# LooSensorNodeV1.net
KiCad netlist of a schematic drawn in EAGLE
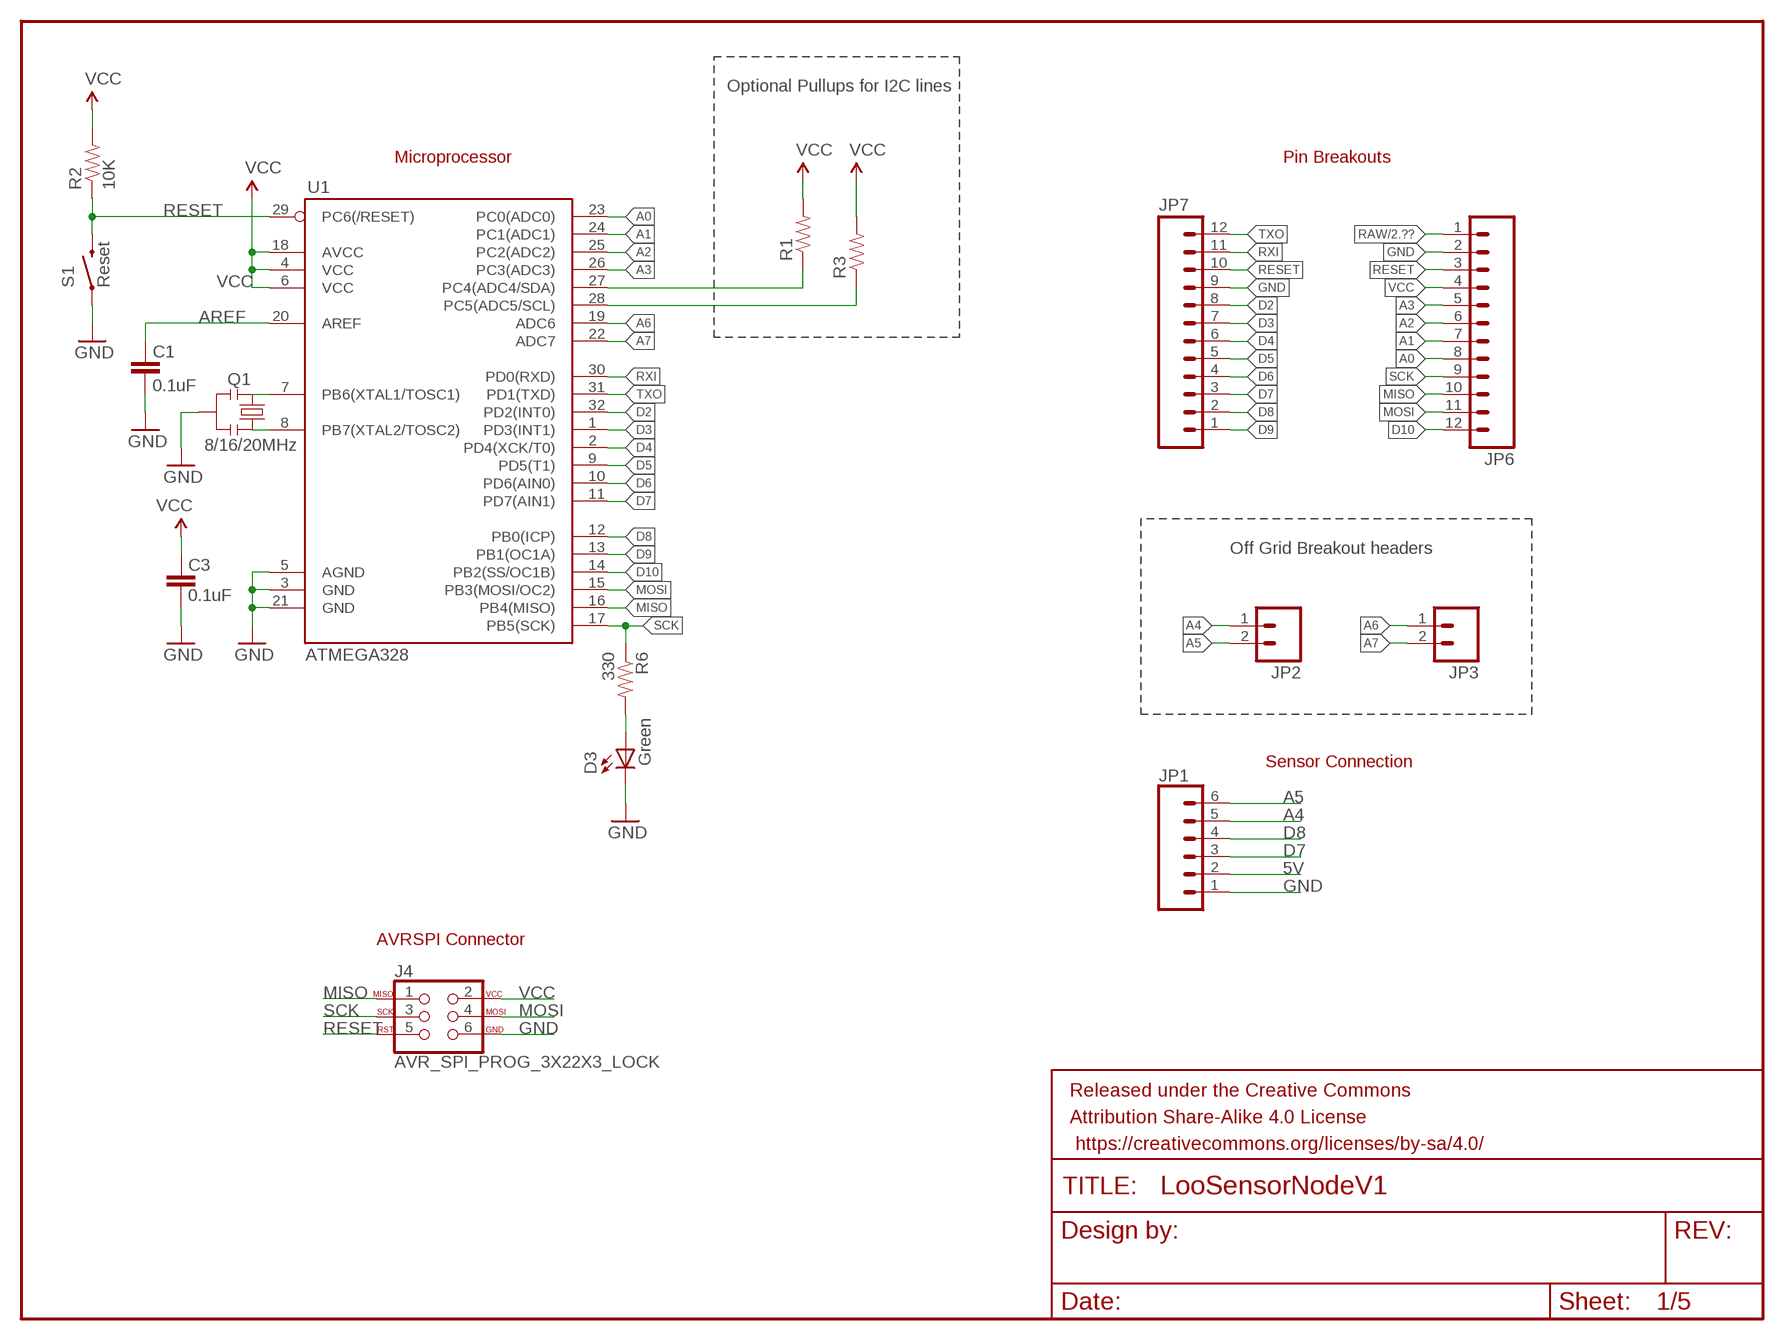
[diagram p0: schematic, sheet 1]
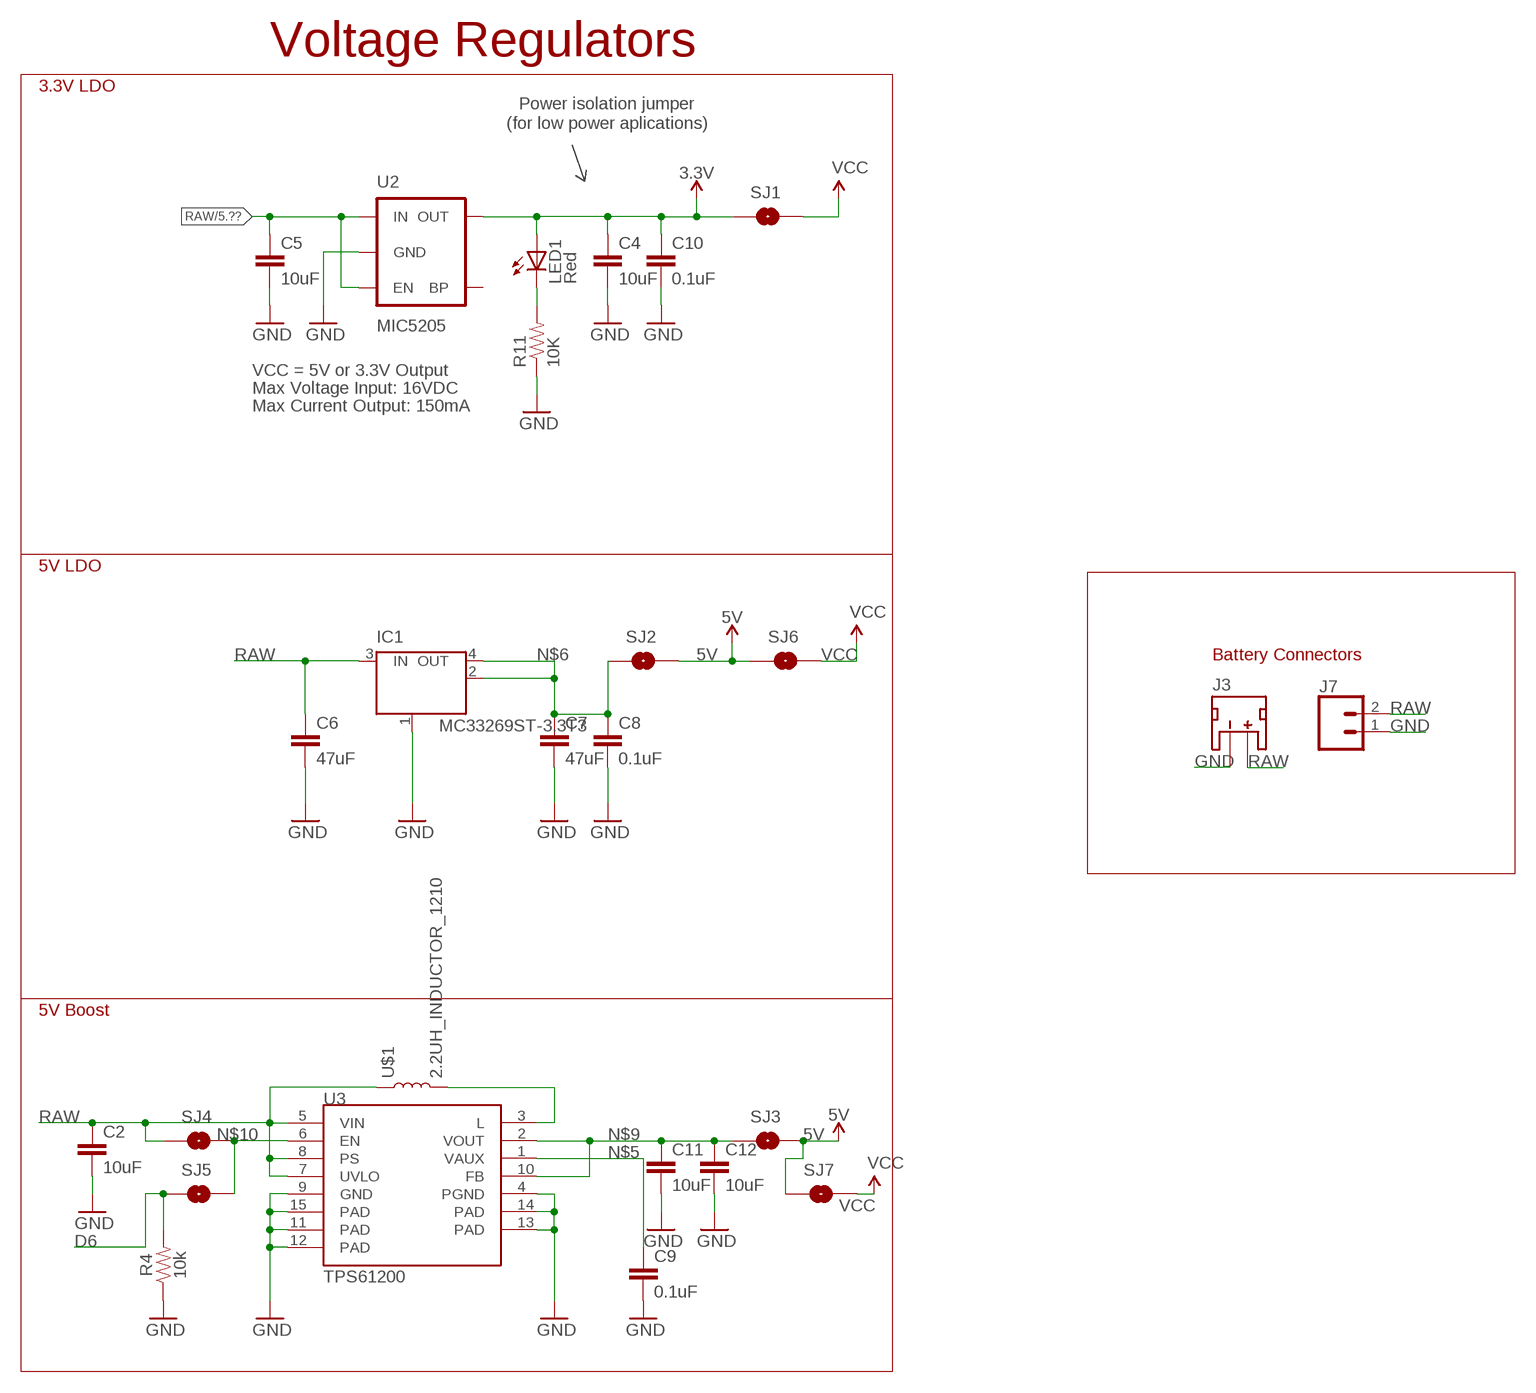
[diagram p1: schematic, sheet 2]
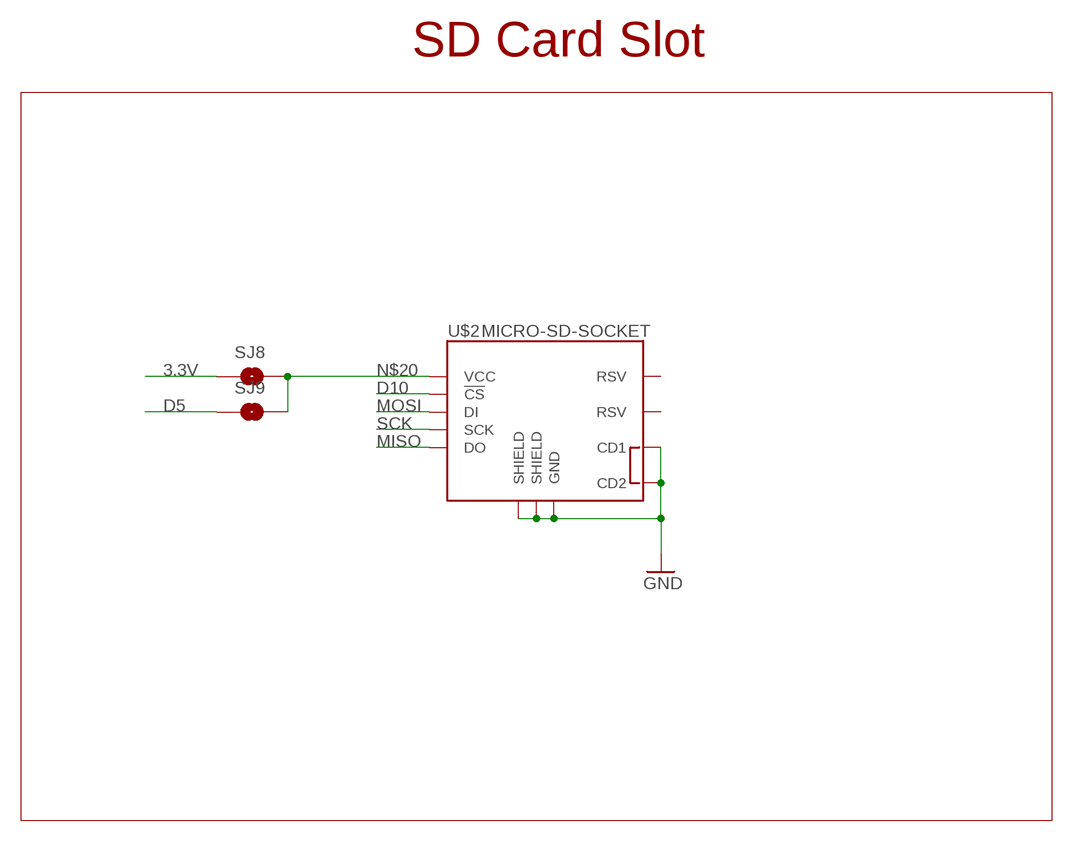
[diagram p2: schematic, sheet 3]
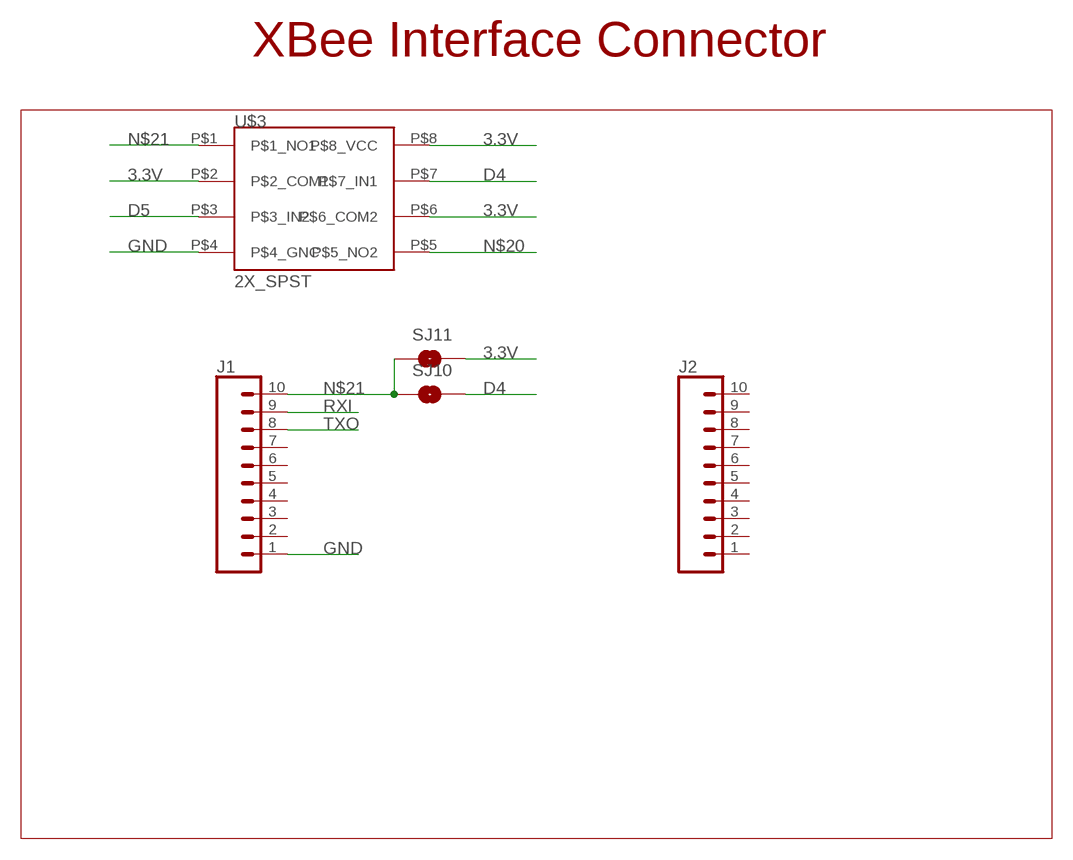
[diagram p3: schematic, sheet 4]
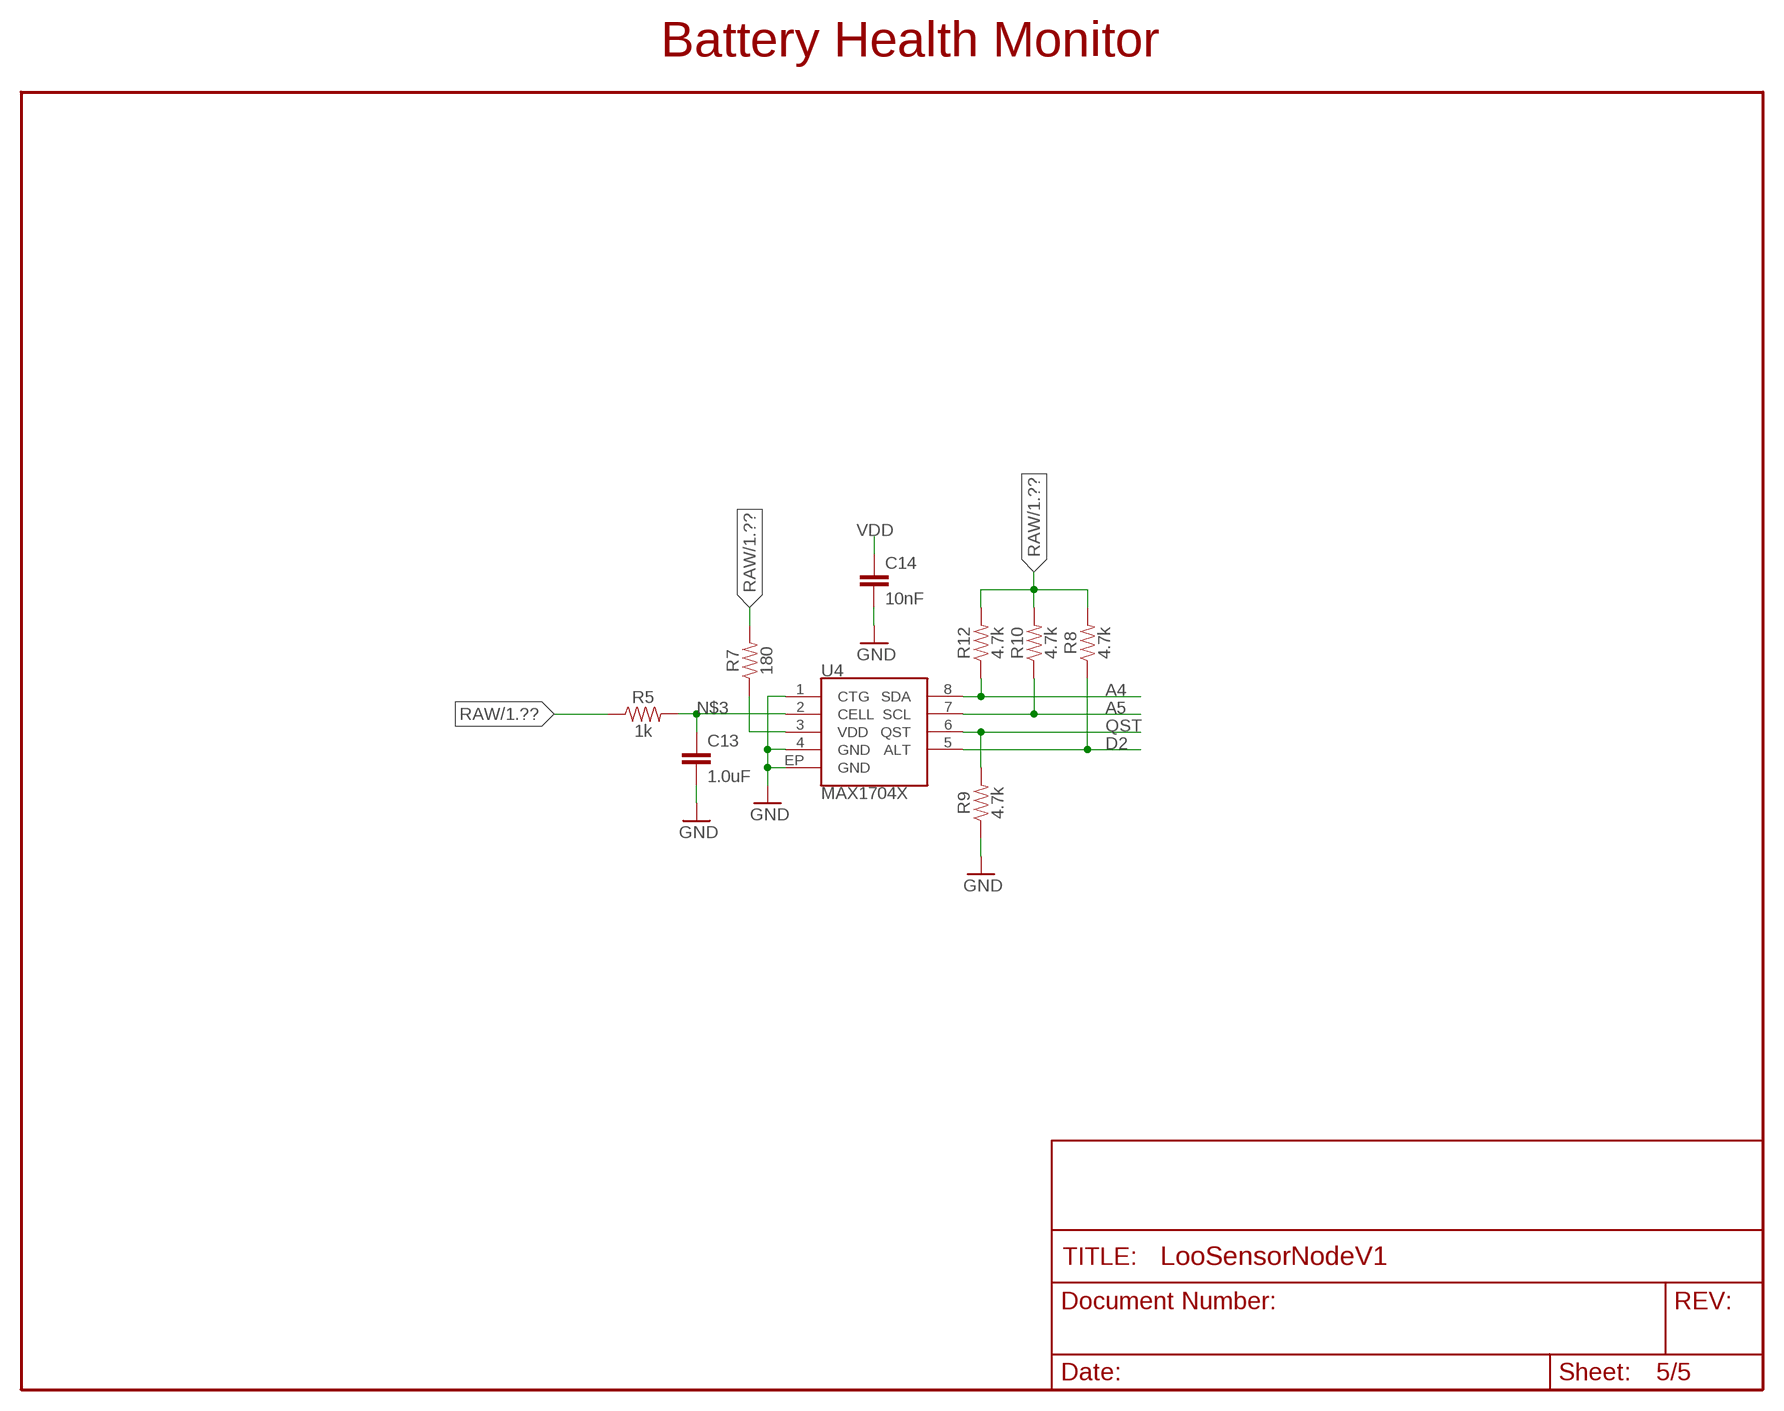
[diagram p4: schematic, sheet 5]

(export (version "E")
  (design (tool "Eeschema 10.0.6"))
  (components
    (comp (ref "C1")
      (value "0.1uF")
      (footprint "eagle-import:0603-CAP")
      (libsource (lib "eagle-import") (part "CAP0603-CAP"))
    )
    (comp (ref "C3")
      (value "0.1uF")
      (footprint "eagle-import:0603-CAP")
      (libsource (lib "eagle-import") (part "CAP0603-CAP"))
    )
    (comp (ref "D3")
      (value "Green")
      (footprint "eagle-import:0603-LED-ALT1")
      (libsource (lib "eagle-import") (part "LED"))
    )
    (comp (ref "FRAME1")
      (value "FRAME-LETTER")
      (footprint "eagle-import:CREATIVE_COMMONS")
      (libsource (lib "eagle-import") (part "SparkFun-Aesthetics_FRAME-LETTER"))
    )
    (comp (ref "J4")
      (value "AVR_SPI_PROG_3X22X3_LOCK")
      (footprint "eagle-import:2X3_LOCK")
      (libsource (lib "eagle-import") (part "AVR_SPI_PROG_3X22X3_LOCK"))
    )
    (comp (ref "JP1")
      (value "CONN_06SILK_FEMALE_PTH")
      (footprint "eagle-import:1X06")
      (libsource (lib "eagle-import") (part "CONN_06SILK_FEMALE_PTH"))
    )
    (comp (ref "JP2")
      (value "M02PTH")
      (footprint "eagle-import:1X02")
      (libsource (lib "eagle-import") (part "M02PTH"))
    )
    (comp (ref "JP3")
      (value "M02PTH")
      (footprint "eagle-import:1X02")
      (libsource (lib "eagle-import") (part "M02PTH"))
    )
    (comp (ref "JP6")
      (value "M12PTH")
      (footprint "eagle-import:1X12")
      (libsource (lib "eagle-import") (part "M12PTH"))
    )
    (comp (ref "JP7")
      (value "M12PTH")
      (footprint "eagle-import:1X12")
      (libsource (lib "eagle-import") (part "M12PTH"))
    )
    (comp (ref "Q1")
      (value "8/16/20MHz")
      (footprint "eagle-import:RESONATOR-SMD-1_1")
      (libsource (lib "eagle-import") (part "RESONATOR1{colon}1"))
    )
    (comp (ref "R1")
      (value "RESISTOR0603-RES")
      (footprint "eagle-import:0603-RES")
      (libsource (lib "eagle-import") (part "RESISTOR0603-RES"))
    )
    (comp (ref "R2")
      (value "10K")
      (footprint "eagle-import:0603-RES")
      (libsource (lib "eagle-import") (part "RESISTOR0603-RES"))
    )
    (comp (ref "R3")
      (value "RESISTOR0603-RES")
      (footprint "eagle-import:0603-RES")
      (libsource (lib "eagle-import") (part "RESISTOR0603-RES"))
    )
    (comp (ref "R6")
      (value "330")
      (footprint "eagle-import:0603-RES")
      (libsource (lib "eagle-import") (part "RESISTOR0603-RES"))
    )
    (comp (ref "S1")
      (value "Reset")
      (footprint "eagle-import:TACTILE-SWITCH-SMD-ALT01")
      (libsource (lib "eagle-import") (part "SWITCH-MOMENTARY-2SMD-ALT01"))
    )
    (comp (ref "U1")
      (value "ATMEGA328")
      (footprint "eagle-import:TQFP32-08")
      (libsource (lib "eagle-import") (part "ATMEGA168"))
    )
    (comp (ref "SJ8")
      (value "SOLDERJUMPERNC")
      (footprint "eagle-import:SJ_2S")
      (libsource (lib "eagle-import") (part "SOLDERJUMPERNC"))
    )
    (comp (ref "SJ9")
      (value "SOLDERJUMPERNC")
      (footprint "eagle-import:SJ_2S")
      (libsource (lib "eagle-import") (part "SOLDERJUMPERNC"))
    )
    (comp (ref "U$2")
      (value "MICRO-SD-SOCKET")
      (footprint "eagle-import:MICRO-SD-SOCKET")
      (libsource (lib "eagle-import") (part "MICRO-SD-SOCKET"))
    )
    (comp (ref "C13")
      (value "1.0uF")
      (footprint "eagle-import:0603")
      (libsource (lib "eagle-import") (part "1.0UF-0603-16V-10%"))
    )
    (comp (ref "C14")
      (value "10nF")
      (footprint "eagle-import:0603")
      (libsource (lib "eagle-import") (part "10NF-0603-50V-10%"))
    )
    (comp (ref "R5")
      (value "1k")
      (footprint "eagle-import:0603")
      (libsource (lib "eagle-import") (part "1KOHM-0603-1/10W-1%"))
    )
    (comp (ref "R7")
      (value "180")
      (footprint "eagle-import:0603")
      (libsource (lib "eagle-import") (part "180OHM-0603-1/10W-1%"))
    )
    (comp (ref "R8")
      (value "4.7k")
      (footprint "eagle-import:0603")
      (libsource (lib "eagle-import") (part "4.7KOHM-0603-1/10W-1%"))
    )
    (comp (ref "R9")
      (value "4.7k")
      (footprint "eagle-import:0603")
      (libsource (lib "eagle-import") (part "4.7KOHM-0603-1/10W-1%"))
    )
    (comp (ref "R10")
      (value "4.7k")
      (footprint "eagle-import:0603")
      (libsource (lib "eagle-import") (part "4.7KOHM-0603-1/10W-1%"))
    )
    (comp (ref "R12")
      (value "4.7k")
      (footprint "eagle-import:0603")
      (libsource (lib "eagle-import") (part "4.7KOHM-0603-1/10W-1%"))
    )
    (comp (ref "U4")
      (value "MAX1704X")
      (footprint "eagle-import:TDFN-8")
      (libsource (lib "eagle-import") (part "MAX1704X"))
    )
    (comp (ref "J1")
      (value "CONN_102MM")
      (footprint "eagle-import:1X10-2MM")
      (libsource (lib "eagle-import") (part "CONN_102MM"))
    )
    (comp (ref "J2")
      (value "CONN_102MM")
      (footprint "eagle-import:1X10-2MM")
      (libsource (lib "eagle-import") (part "CONN_102MM"))
    )
    (comp (ref "SJ10")
      (value "SOLDERJUMPERNC")
      (footprint "eagle-import:SJ_2S")
      (libsource (lib "eagle-import") (part "SOLDERJUMPERNC"))
    )
    (comp (ref "SJ11")
      (value "SOLDERJUMPERNC")
      (footprint "eagle-import:SJ_2S")
      (libsource (lib "eagle-import") (part "SOLDERJUMPERNC"))
    )
    (comp (ref "U$3")
      (value "2X_SPST")
      (footprint "eagle-import:2X_SPST")
      (libsource (lib "eagle-import") (part "2X_SPST"))
    )
    (comp (ref "C2")
      (value "10uF")
      (footprint "eagle-import:0603")
      (libsource (lib "eagle-import") (part "10UF-0603-6.3V-20%"))
    )
    (comp (ref "C4")
      (value "10uF")
      (footprint "eagle-import:0603")
      (libsource (lib "eagle-import") (part "10UF-0603-6.3V-20%"))
    )
    (comp (ref "C5")
      (value "10uF")
      (footprint "eagle-import:0603")
      (libsource (lib "eagle-import") (part "10UF-0603-6.3V-20%"))
    )
    (comp (ref "C6")
      (value "47uF")
      (footprint "eagle-import:1210")
      (libsource (lib "eagle-import") (part "10UF-1210-50V-20%"))
    )
    (comp (ref "C7")
      (value "47uF")
      (footprint "eagle-import:1210")
      (libsource (lib "eagle-import") (part "10UF-1210-50V-20%"))
    )
    (comp (ref "C8")
      (value "0.1uF")
      (footprint "eagle-import:0603")
      (libsource (lib "eagle-import") (part "0.1UF-0603-25V-5%"))
    )
    (comp (ref "C9")
      (value "0.1uF")
      (footprint "eagle-import:0603")
      (libsource (lib "eagle-import") (part "0.1UF-0603-25V-5%"))
    )
    (comp (ref "C10")
      (value "0.1uF")
      (footprint "eagle-import:0603-CAP")
      (libsource (lib "eagle-import") (part "CAP0603-CAP"))
    )
    (comp (ref "C11")
      (value "10uF")
      (footprint "eagle-import:0603")
      (libsource (lib "eagle-import") (part "10UF-0603-6.3V-20%"))
    )
    (comp (ref "C12")
      (value "10uF")
      (footprint "eagle-import:0603")
      (libsource (lib "eagle-import") (part "10UF-0603-6.3V-20%"))
    )
    (comp (ref "IC1")
      (value "MC33269ST-3.3T3")
      (footprint "eagle-import:SOT223")
      (libsource (lib "eagle-import") (part "MC33269ST-3.3T3"))
    )
    (comp (ref "J3")
      (value "JST_2MM_MALE")
      (footprint "eagle-import:JST-2-SMD")
      (libsource (lib "eagle-import") (part "JST_2MM_MALE"))
    )
    (comp (ref "J7")
      (value "CONN_02")
      (footprint "eagle-import:1X02")
      (libsource (lib "eagle-import") (part "CONN_02"))
    )
    (comp (ref "LED1")
      (value "Red")
      (footprint "eagle-import:0603-LED-ALT1")
      (libsource (lib "eagle-import") (part "LED"))
    )
    (comp (ref "R4")
      (value "10k")
      (footprint "eagle-import:0603")
      (libsource (lib "eagle-import") (part "10KOHM-0603-1/10W-1%"))
    )
    (comp (ref "R11")
      (value "10K")
      (footprint "eagle-import:0603-RES")
      (libsource (lib "eagle-import") (part "RESISTOR0603-RES"))
    )
    (comp (ref "SJ1")
      (value "SOLDERJUMPERNC")
      (footprint "eagle-import:SJ_2S")
      (libsource (lib "eagle-import") (part "SOLDERJUMPERNC"))
    )
    (comp (ref "SJ2")
      (value "SOLDERJUMPERNC")
      (footprint "eagle-import:SJ_2S")
      (libsource (lib "eagle-import") (part "SOLDERJUMPERNC"))
    )
    (comp (ref "SJ3")
      (value "SOLDERJUMPERNC")
      (footprint "eagle-import:SJ_2S")
      (libsource (lib "eagle-import") (part "SOLDERJUMPERNC"))
    )
    (comp (ref "SJ4")
      (value "SOLDERJUMPERNC")
      (footprint "eagle-import:SJ_2S")
      (libsource (lib "eagle-import") (part "SOLDERJUMPERNC"))
    )
    (comp (ref "SJ5")
      (value "SOLDERJUMPERNC")
      (footprint "eagle-import:SJ_2S")
      (libsource (lib "eagle-import") (part "SOLDERJUMPERNC"))
    )
    (comp (ref "SJ6")
      (value "SOLDERJUMPERNC")
      (footprint "eagle-import:SJ_2S")
      (libsource (lib "eagle-import") (part "SOLDERJUMPERNC"))
    )
    (comp (ref "SJ7")
      (value "SOLDERJUMPERNC")
      (footprint "eagle-import:SJ_2S")
      (libsource (lib "eagle-import") (part "SOLDERJUMPERNC"))
    )
    (comp (ref "U$1")
      (value "2.2UH_INDUCTOR_1210")
      (footprint "eagle-import:1210")
      (libsource (lib "eagle-import") (part "2.2UH_INDUCTOR_1210"))
    )
    (comp (ref "U2")
      (value "MIC5205")
      (footprint "eagle-import:SOT23-5")
      (libsource (lib "eagle-import") (part "V_REG_LDOSMD"))
    )
    (comp (ref "U3")
      (value "TPS61200")
      (footprint "eagle-import:QFN-10_PAD")
      (libsource (lib "eagle-import") (part "TPS61200"))
    )
  )
  (nets
    (net (code "1") (name "3.3V") (class "Default")
      (node (ref "C10") (pin "1") (pinfunction "1_1") (pintype "passive"))
      (node (ref "C4") (pin "1") (pinfunction "1_1") (pintype "passive"))
      (node (ref "LED1") (pin "A") (pinfunction "A_A") (pintype "passive"))
      (node (ref "SJ1") (pin "1") (pinfunction "1_1") (pintype "passive"))
      (node (ref "SJ11") (pin "2") (pinfunction "2_2") (pintype "passive"))
      (node (ref "SJ8") (pin "1") (pinfunction "1_1") (pintype "passive"))
      (node (ref "U$3") (pin "P$2") (pinfunction "P$2_COM1_P$2") (pintype "bidirectional"))
      (node (ref "U$3") (pin "P$6") (pinfunction "P$6_COM2_P$6") (pintype "bidirectional"))
      (node (ref "U$3") (pin "P$8") (pinfunction "P$8_VCC_P$8") (pintype "bidirectional"))
      (node (ref "U2") (pin "5") (pinfunction "OUT_5") (pintype "passive"))
    )
    (net (code "2") (name "5V") (class "Default")
      (node (ref "JP1") (pin "2") (pinfunction "2_2") (pintype "passive"))
      (node (ref "SJ2") (pin "2") (pinfunction "2_2") (pintype "passive"))
      (node (ref "SJ3") (pin "2") (pinfunction "2_2") (pintype "passive"))
      (node (ref "SJ6") (pin "1") (pinfunction "1_1") (pintype "passive"))
      (node (ref "SJ7") (pin "1") (pinfunction "1_1") (pintype "passive"))
    )
    (net (code "3") (name "A0") (class "Default")
      (node (ref "JP6") (pin "8") (pinfunction "8_8") (pintype "passive"))
      (node (ref "U1") (pin "23") (pinfunction "PC0(ADC0)_23") (pintype "bidirectional"))
    )
    (net (code "4") (name "A1") (class "Default")
      (node (ref "JP6") (pin "7") (pinfunction "7_7") (pintype "passive"))
      (node (ref "U1") (pin "24") (pinfunction "PC1(ADC1)_24") (pintype "bidirectional"))
    )
    (net (code "5") (name "A2") (class "Default")
      (node (ref "JP6") (pin "6") (pinfunction "6_6") (pintype "passive"))
      (node (ref "U1") (pin "25") (pinfunction "PC2(ADC2)_25") (pintype "bidirectional"))
    )
    (net (code "6") (name "A3") (class "Default")
      (node (ref "JP6") (pin "5") (pinfunction "5_5") (pintype "passive"))
      (node (ref "U1") (pin "26") (pinfunction "PC3(ADC3)_26") (pintype "bidirectional"))
    )
    (net (code "7") (name "A4") (class "Default")
      (node (ref "JP1") (pin "5") (pinfunction "5_5") (pintype "passive"))
      (node (ref "JP2") (pin "1") (pinfunction "1_1") (pintype "passive"))
      (node (ref "R1") (pin "1") (pinfunction "1_1") (pintype "passive"))
      (node (ref "R12") (pin "1") (pinfunction "1_1") (pintype "passive"))
      (node (ref "U1") (pin "27") (pinfunction "PC4(ADC4/SDA)_27") (pintype "bidirectional"))
      (node (ref "U4") (pin "8") (pinfunction "SDA_8") (pintype "bidirectional"))
    )
    (net (code "8") (name "A5") (class "Default")
      (node (ref "JP1") (pin "6") (pinfunction "6_6") (pintype "passive"))
      (node (ref "JP2") (pin "2") (pinfunction "2_2") (pintype "passive"))
      (node (ref "R10") (pin "1") (pinfunction "1_1") (pintype "passive"))
      (node (ref "R3") (pin "1") (pinfunction "1_1") (pintype "passive"))
      (node (ref "U1") (pin "28") (pinfunction "PC5(ADC5/SCL)_28") (pintype "bidirectional"))
      (node (ref "U4") (pin "7") (pinfunction "SCL_7") (pintype "bidirectional"))
    )
    (net (code "9") (name "A6") (class "Default")
      (node (ref "JP3") (pin "1") (pinfunction "1_1") (pintype "passive"))
      (node (ref "U1") (pin "19") (pinfunction "ADC6_19") (pintype "bidirectional"))
    )
    (net (code "10") (name "A7") (class "Default")
      (node (ref "JP3") (pin "2") (pinfunction "2_2") (pintype "passive"))
      (node (ref "U1") (pin "22") (pinfunction "ADC7_22") (pintype "bidirectional"))
    )
    (net (code "11") (name "AREF") (class "Default")
      (node (ref "C1") (pin "2") (pinfunction "2_2") (pintype "passive"))
      (node (ref "U1") (pin "20") (pinfunction "AREF_20") (pintype "bidirectional"))
    )
    (net (code "12") (name "D2") (class "Default")
      (node (ref "JP7") (pin "8") (pinfunction "8_8") (pintype "passive"))
      (node (ref "R8") (pin "1") (pinfunction "1_1") (pintype "passive"))
      (node (ref "U1") (pin "32") (pinfunction "PD2(INT0)_32") (pintype "bidirectional"))
      (node (ref "U4") (pin "5") (pinfunction "ALT_5") (pintype "bidirectional"))
    )
    (net (code "13") (name "D3") (class "Default")
      (node (ref "JP7") (pin "7") (pinfunction "7_7") (pintype "passive"))
      (node (ref "U1") (pin "1") (pinfunction "PD3(INT1)_1") (pintype "bidirectional"))
    )
    (net (code "14") (name "D4") (class "Default")
      (node (ref "JP7") (pin "6") (pinfunction "6_6") (pintype "passive"))
      (node (ref "SJ10") (pin "2") (pinfunction "2_2") (pintype "passive"))
      (node (ref "U$3") (pin "P$7") (pinfunction "P$7_IN1_P$7") (pintype "bidirectional"))
      (node (ref "U1") (pin "2") (pinfunction "PD4(XCK/T0)_2") (pintype "bidirectional"))
    )
    (net (code "15") (name "D5") (class "Default")
      (node (ref "JP7") (pin "5") (pinfunction "5_5") (pintype "passive"))
      (node (ref "SJ9") (pin "1") (pinfunction "1_1") (pintype "passive"))
      (node (ref "U$3") (pin "P$3") (pinfunction "P$3_IN2_P$3") (pintype "bidirectional"))
      (node (ref "U1") (pin "9") (pinfunction "PD5(T1)_9") (pintype "bidirectional"))
    )
    (net (code "16") (name "D6") (class "Default")
      (node (ref "JP7") (pin "4") (pinfunction "4_4") (pintype "passive"))
      (node (ref "R4") (pin "2") (pinfunction "2_2") (pintype "passive"))
      (node (ref "SJ5") (pin "1") (pinfunction "1_1") (pintype "passive"))
      (node (ref "U1") (pin "10") (pinfunction "PD6(AIN0)_10") (pintype "bidirectional"))
    )
    (net (code "17") (name "D7") (class "Default")
      (node (ref "JP1") (pin "3") (pinfunction "3_3") (pintype "passive"))
      (node (ref "JP7") (pin "3") (pinfunction "3_3") (pintype "passive"))
      (node (ref "U1") (pin "11") (pinfunction "PD7(AIN1)_11") (pintype "bidirectional"))
    )
    (net (code "18") (name "D8") (class "Default")
      (node (ref "JP1") (pin "4") (pinfunction "4_4") (pintype "passive"))
      (node (ref "JP7") (pin "2") (pinfunction "2_2") (pintype "passive"))
      (node (ref "U1") (pin "12") (pinfunction "PB0(ICP)_12") (pintype "bidirectional"))
    )
    (net (code "19") (name "D9") (class "Default")
      (node (ref "JP7") (pin "1") (pinfunction "1_1") (pintype "passive"))
      (node (ref "U1") (pin "13") (pinfunction "PB1(OC1A)_13") (pintype "bidirectional"))
    )
    (net (code "20") (name "D10") (class "Default")
      (node (ref "JP6") (pin "12") (pinfunction "12_12") (pintype "passive"))
      (node (ref "U$2") (pin "CS") (pinfunction "~{CS}_CS") (pintype "bidirectional"))
      (node (ref "U1") (pin "14") (pinfunction "PB2(SS/OC1B)_14") (pintype "bidirectional"))
    )
    (net (code "21") (name "GND") (class "Default")
      (node (ref "C1") (pin "1") (pinfunction "1_1") (pintype "passive"))
      (node (ref "C10") (pin "2") (pinfunction "2_2") (pintype "passive"))
      (node (ref "C11") (pin "2") (pinfunction "2_2") (pintype "passive"))
      (node (ref "C12") (pin "2") (pinfunction "2_2") (pintype "passive"))
      (node (ref "C13") (pin "2") (pinfunction "2_2") (pintype "passive"))
      (node (ref "C14") (pin "2") (pinfunction "2_2") (pintype "passive"))
      (node (ref "C2") (pin "2") (pinfunction "2_2") (pintype "passive"))
      (node (ref "C3") (pin "1") (pinfunction "1_1") (pintype "passive"))
      (node (ref "C4") (pin "2") (pinfunction "2_2") (pintype "passive"))
      (node (ref "C5") (pin "2") (pinfunction "2_2") (pintype "passive"))
      (node (ref "C6") (pin "2") (pinfunction "2_2") (pintype "passive"))
      (node (ref "C7") (pin "2") (pinfunction "2_2") (pintype "passive"))
      (node (ref "C8") (pin "2") (pinfunction "2_2") (pintype "passive"))
      (node (ref "C9") (pin "2") (pinfunction "2_2") (pintype "passive"))
      (node (ref "D3") (pin "C") (pinfunction "C_C") (pintype "passive"))
      (node (ref "IC1") (pin "1") (pinfunction "GND/ADJ_1") (pintype "input"))
      (node (ref "J1") (pin "1") (pinfunction "1_1") (pintype "passive"))
      (node (ref "J3") (pin "1") (pinfunction "-_1") (pintype "bidirectional"))
      (node (ref "J4") (pin "6") (pinfunction "6_6") (pintype "passive"))
      (node (ref "J7") (pin "1") (pinfunction "1_1") (pintype "passive"))
      (node (ref "JP1") (pin "1") (pinfunction "1_1") (pintype "passive"))
      (node (ref "JP6") (pin "2") (pinfunction "2_2") (pintype "passive"))
      (node (ref "JP7") (pin "9") (pinfunction "9_9") (pintype "passive"))
      (node (ref "Q1") (pin "2") (pinfunction "2_2") (pintype "passive"))
      (node (ref "R11") (pin "1") (pinfunction "1_1") (pintype "passive"))
      (node (ref "R4") (pin "1") (pinfunction "1_1") (pintype "passive"))
      (node (ref "R9") (pin "1") (pinfunction "1_1") (pintype "passive"))
      (node (ref "S1") (pin "1") (pinfunction "1_1") (pintype "passive"))
      (node (ref "S1") (pin "2") (pinfunction "1_2") (pintype "passive"))
      (node (ref "U$2") (pin "CD1") (pinfunction "CD1_CD1") (pintype "bidirectional"))
      (node (ref "U$2") (pin "CD2") (pinfunction "CD2_CD2") (pintype "bidirectional"))
      (node (ref "U$2") (pin "GND") (pinfunction "GND_GND") (pintype "bidirectional"))
      (node (ref "U$2") (pin "GND1") (pinfunction "SHIELD_GND1") (pintype "bidirectional"))
      (node (ref "U$2") (pin "GND3") (pinfunction "SHIELD_GND3") (pintype "bidirectional"))
      (node (ref "U$3") (pin "P$4") (pinfunction "P$4_GNC_P$4") (pintype "bidirectional"))
      (node (ref "U1") (pin "21") (pinfunction "GND_21") (pintype "bidirectional"))
      (node (ref "U1") (pin "3") (pinfunction "GND_3") (pintype "bidirectional"))
      (node (ref "U1") (pin "5") (pinfunction "AGND_5") (pintype "bidirectional"))
      (node (ref "U2") (pin "2") (pinfunction "GND_2") (pintype "input"))
      (node (ref "U3") (pin "11") (pinfunction "PAD_11") (pintype "power_in"))
      (node (ref "U3") (pin "12") (pinfunction "PAD_12") (pintype "power_in"))
      (node (ref "U3") (pin "13") (pinfunction "PAD_13") (pintype "power_in"))
      (node (ref "U3") (pin "14") (pinfunction "PAD_14") (pintype "power_in"))
      (node (ref "U3") (pin "15") (pinfunction "PAD_15") (pintype "power_in"))
      (node (ref "U3") (pin "4") (pinfunction "PGND_4") (pintype "power_in"))
      (node (ref "U3") (pin "9") (pinfunction "GND_9") (pintype "power_in"))
      (node (ref "U4") (pin "1") (pinfunction "CTG_1") (pintype "bidirectional"))
      (node (ref "U4") (pin "4") (pinfunction "GND_4") (pintype "bidirectional"))
      (node (ref "U4") (pin "EP") (pinfunction "GND_EP") (pintype "bidirectional"))
    )
    (net (code "22") (name "MISO") (class "Default")
      (node (ref "J4") (pin "1") (pinfunction "1_1") (pintype "passive"))
      (node (ref "JP6") (pin "10") (pinfunction "10_10") (pintype "passive"))
      (node (ref "U$2") (pin "DO") (pinfunction "DO_DO") (pintype "bidirectional"))
      (node (ref "U1") (pin "16") (pinfunction "PB4(MISO)_16") (pintype "bidirectional"))
    )
    (net (code "23") (name "MOSI") (class "Default")
      (node (ref "J4") (pin "4") (pinfunction "4_4") (pintype "passive"))
      (node (ref "JP6") (pin "11") (pinfunction "11_11") (pintype "passive"))
      (node (ref "U$2") (pin "DI") (pinfunction "DI_DI") (pintype "bidirectional"))
      (node (ref "U1") (pin "15") (pinfunction "PB3(MOSI/OC2)_15") (pintype "bidirectional"))
    )
    (net (code "24") (name "N$3") (class "Default")
      (node (ref "C13") (pin "1") (pinfunction "1_1") (pintype "passive"))
      (node (ref "R5") (pin "2") (pinfunction "2_2") (pintype "passive"))
      (node (ref "U4") (pin "2") (pinfunction "CELL_2") (pintype "bidirectional"))
    )
    (net (code "25") (name "N$5") (class "Default")
      (node (ref "C9") (pin "1") (pinfunction "1_1") (pintype "passive"))
      (node (ref "U3") (pin "1") (pinfunction "VAUX_1") (pintype "passive"))
    )
    (net (code "26") (name "N$6") (class "Default")
      (node (ref "C7") (pin "1") (pinfunction "1_1") (pintype "passive"))
      (node (ref "C8") (pin "1") (pinfunction "1_1") (pintype "passive"))
      (node (ref "IC1") (pin "2") (pinfunction "OUT_2") (pintype "passive"))
      (node (ref "IC1") (pin "4") (pinfunction "OUT_4") (pintype "passive"))
      (node (ref "SJ2") (pin "1") (pinfunction "1_1") (pintype "passive"))
    )
    (net (code "27") (name "N$9") (class "Default")
      (node (ref "C11") (pin "1") (pinfunction "1_1") (pintype "passive"))
      (node (ref "C12") (pin "1") (pinfunction "1_1") (pintype "passive"))
      (node (ref "SJ3") (pin "1") (pinfunction "1_1") (pintype "passive"))
      (node (ref "U3") (pin "10") (pinfunction "FB_10") (pintype "passive"))
      (node (ref "U3") (pin "2") (pinfunction "VOUT_2") (pintype "passive"))
    )
    (net (code "28") (name "N$10") (class "Default")
      (node (ref "SJ4") (pin "2") (pinfunction "2_2") (pintype "passive"))
      (node (ref "SJ5") (pin "2") (pinfunction "2_2") (pintype "passive"))
      (node (ref "U3") (pin "6") (pinfunction "EN_6") (pintype "input"))
    )
    (net (code "29") (name "N$20") (class "Default")
      (node (ref "SJ8") (pin "2") (pinfunction "2_2") (pintype "passive"))
      (node (ref "SJ9") (pin "2") (pinfunction "2_2") (pintype "passive"))
      (node (ref "U$2") (pin "VCC") (pinfunction "VCC_VCC") (pintype "bidirectional"))
      (node (ref "U$3") (pin "P$5") (pinfunction "P$5_NO2_P$5") (pintype "bidirectional"))
    )
    (net (code "30") (name "N$21") (class "Default")
      (node (ref "J1") (pin "10") (pinfunction "10_10") (pintype "passive"))
      (node (ref "SJ10") (pin "1") (pinfunction "1_1") (pintype "passive"))
      (node (ref "SJ11") (pin "1") (pinfunction "1_1") (pintype "passive"))
      (node (ref "U$3") (pin "P$1") (pinfunction "P$1_NO1_P$1") (pintype "bidirectional"))
    )
    (net (code "31") (name "Net-(D3-PadA)") (class "Default")
      (node (ref "D3") (pin "A") (pinfunction "A_A") (pintype "passive"))
      (node (ref "R6") (pin "2") (pinfunction "2_2") (pintype "passive"))
    )
    (net (code "32") (name "Net-(LED1-PadC)") (class "Default")
      (node (ref "LED1") (pin "C") (pinfunction "C_C") (pintype "passive"))
      (node (ref "R11") (pin "2") (pinfunction "2_2") (pintype "passive"))
    )
    (net (code "33") (name "Net-(U1-PB6(XTAL1{slash}TOSC1))") (class "Default")
      (node (ref "Q1") (pin "1") (pinfunction "1_1") (pintype "passive"))
      (node (ref "U1") (pin "7") (pinfunction "PB6(XTAL1/TOSC1)_7") (pintype "bidirectional"))
    )
    (net (code "34") (name "Net-(U1-PB7(XTAL2{slash}TOSC2))") (class "Default")
      (node (ref "Q1") (pin "3") (pinfunction "3_3") (pintype "passive"))
      (node (ref "U1") (pin "8") (pinfunction "PB7(XTAL2/TOSC2)_8") (pintype "bidirectional"))
    )
    (net (code "35") (name "Net-(U3-L)") (class "Default")
      (node (ref "U$1") (pin "2") (pinfunction "2_2") (pintype "passive"))
      (node (ref "U3") (pin "3") (pinfunction "L_3") (pintype "passive"))
    )
    (net (code "36") (name "QST") (class "Default")
      (node (ref "R9") (pin "2") (pinfunction "2_2") (pintype "passive"))
      (node (ref "U4") (pin "6") (pinfunction "QST_6") (pintype "bidirectional"))
    )
    (net (code "37") (name "RAW") (class "Default")
      (node (ref "C2") (pin "1") (pinfunction "1_1") (pintype "passive"))
      (node (ref "C5") (pin "1") (pinfunction "1_1") (pintype "passive"))
      (node (ref "C6") (pin "1") (pinfunction "1_1") (pintype "passive"))
      (node (ref "IC1") (pin "3") (pinfunction "IN_3") (pintype "input"))
      (node (ref "J3") (pin "2") (pinfunction "+_2") (pintype "bidirectional"))
      (node (ref "J7") (pin "2") (pinfunction "2_2") (pintype "passive"))
      (node (ref "JP6") (pin "1") (pinfunction "1_1") (pintype "passive"))
      (node (ref "R10") (pin "2") (pinfunction "2_2") (pintype "passive"))
      (node (ref "R12") (pin "2") (pinfunction "2_2") (pintype "passive"))
      (node (ref "R5") (pin "1") (pinfunction "1_1") (pintype "passive"))
      (node (ref "R7") (pin "2") (pinfunction "2_2") (pintype "passive"))
      (node (ref "R8") (pin "2") (pinfunction "2_2") (pintype "passive"))
      (node (ref "SJ4") (pin "1") (pinfunction "1_1") (pintype "passive"))
      (node (ref "U$1") (pin "1") (pinfunction "1_1") (pintype "passive"))
      (node (ref "U2") (pin "1") (pinfunction "IN_1") (pintype "input"))
      (node (ref "U2") (pin "3") (pinfunction "EN_3") (pintype "input"))
      (node (ref "U3") (pin "5") (pinfunction "VIN_5") (pintype "power_in"))
      (node (ref "U3") (pin "7") (pinfunction "UVLO_7") (pintype "passive"))
      (node (ref "U3") (pin "8") (pinfunction "PS_8") (pintype "input"))
    )
    (net (code "38") (name "RESET") (class "Default")
      (node (ref "J4") (pin "5") (pinfunction "5_5") (pintype "passive"))
      (node (ref "JP6") (pin "3") (pinfunction "3_3") (pintype "passive"))
      (node (ref "JP7") (pin "10") (pinfunction "10_10") (pintype "passive"))
      (node (ref "R2") (pin "1") (pinfunction "1_1") (pintype "passive"))
      (node (ref "S1") (pin "3") (pinfunction "2_3") (pintype "passive"))
      (node (ref "S1") (pin "4") (pinfunction "2_4") (pintype "passive"))
      (node (ref "U1") (pin "29") (pinfunction "PC6(/RESET)_29") (pintype "bidirectional"))
    )
    (net (code "39") (name "RXI") (class "Default")
      (node (ref "J1") (pin "9") (pinfunction "9_9") (pintype "passive"))
      (node (ref "JP7") (pin "11") (pinfunction "11_11") (pintype "passive"))
      (node (ref "U1") (pin "30") (pinfunction "PD0(RXD)_30") (pintype "bidirectional"))
    )
    (net (code "40") (name "SCK") (class "Default")
      (node (ref "J4") (pin "3") (pinfunction "3_3") (pintype "passive"))
      (node (ref "JP6") (pin "9") (pinfunction "9_9") (pintype "passive"))
      (node (ref "R6") (pin "1") (pinfunction "1_1") (pintype "passive"))
      (node (ref "U$2") (pin "SCLK") (pinfunction "SCK_SCLK") (pintype "bidirectional"))
      (node (ref "U1") (pin "17") (pinfunction "PB5(SCK)_17") (pintype "bidirectional"))
    )
    (net (code "41") (name "TXO") (class "Default")
      (node (ref "J1") (pin "8") (pinfunction "8_8") (pintype "passive"))
      (node (ref "JP7") (pin "12") (pinfunction "12_12") (pintype "passive"))
      (node (ref "U1") (pin "31") (pinfunction "PD1(TXD)_31") (pintype "bidirectional"))
    )
    (net (code "42") (name "VCC") (class "Default")
      (node (ref "C3") (pin "2") (pinfunction "2_2") (pintype "passive"))
      (node (ref "J4") (pin "2") (pinfunction "2_2") (pintype "passive"))
      (node (ref "JP6") (pin "4") (pinfunction "4_4") (pintype "passive"))
      (node (ref "R1") (pin "2") (pinfunction "2_2") (pintype "passive"))
      (node (ref "R2") (pin "2") (pinfunction "2_2") (pintype "passive"))
      (node (ref "R3") (pin "2") (pinfunction "2_2") (pintype "passive"))
      (node (ref "SJ1") (pin "2") (pinfunction "2_2") (pintype "passive"))
      (node (ref "SJ6") (pin "2") (pinfunction "2_2") (pintype "passive"))
      (node (ref "SJ7") (pin "2") (pinfunction "2_2") (pintype "passive"))
      (node (ref "U1") (pin "18") (pinfunction "AVCC_18") (pintype "bidirectional"))
      (node (ref "U1") (pin "4") (pinfunction "VCC_4") (pintype "bidirectional"))
      (node (ref "U1") (pin "6") (pinfunction "VCC_6") (pintype "bidirectional"))
    )
    (net (code "43") (name "VDD") (class "Default")
      (node (ref "C14") (pin "1") (pinfunction "1_1") (pintype "passive"))
      (node (ref "R7") (pin "1") (pinfunction "1_1") (pintype "passive"))
      (node (ref "U4") (pin "3") (pinfunction "VDD_3") (pintype "bidirectional"))
    )
    (net (code "44") (name "unconnected-(J1-Pad2)") (class "Default")
      (node (ref "J1") (pin "2") (pinfunction "2_2") (pintype "passive"))
    )
    (net (code "45") (name "unconnected-(J1-Pad3)") (class "Default")
      (node (ref "J1") (pin "3") (pinfunction "3_3") (pintype "passive"))
    )
    (net (code "46") (name "unconnected-(J1-Pad4)") (class "Default")
      (node (ref "J1") (pin "4") (pinfunction "4_4") (pintype "passive"))
    )
    (net (code "47") (name "unconnected-(J1-Pad5)") (class "Default")
      (node (ref "J1") (pin "5") (pinfunction "5_5") (pintype "passive"))
    )
    (net (code "48") (name "unconnected-(J1-Pad6)") (class "Default")
      (node (ref "J1") (pin "6") (pinfunction "6_6") (pintype "passive"))
    )
    (net (code "49") (name "unconnected-(J1-Pad7)") (class "Default")
      (node (ref "J1") (pin "7") (pinfunction "7_7") (pintype "passive"))
    )
    (net (code "50") (name "unconnected-(J2-Pad1)") (class "Default")
      (node (ref "J2") (pin "1") (pinfunction "1_1") (pintype "passive"))
    )
    (net (code "51") (name "unconnected-(J2-Pad2)") (class "Default")
      (node (ref "J2") (pin "2") (pinfunction "2_2") (pintype "passive"))
    )
    (net (code "52") (name "unconnected-(J2-Pad3)") (class "Default")
      (node (ref "J2") (pin "3") (pinfunction "3_3") (pintype "passive"))
    )
    (net (code "53") (name "unconnected-(J2-Pad4)") (class "Default")
      (node (ref "J2") (pin "4") (pinfunction "4_4") (pintype "passive"))
    )
    (net (code "54") (name "unconnected-(J2-Pad5)") (class "Default")
      (node (ref "J2") (pin "5") (pinfunction "5_5") (pintype "passive"))
    )
    (net (code "55") (name "unconnected-(J2-Pad6)") (class "Default")
      (node (ref "J2") (pin "6") (pinfunction "6_6") (pintype "passive"))
    )
    (net (code "56") (name "unconnected-(J2-Pad7)") (class "Default")
      (node (ref "J2") (pin "7") (pinfunction "7_7") (pintype "passive"))
    )
    (net (code "57") (name "unconnected-(J2-Pad8)") (class "Default")
      (node (ref "J2") (pin "8") (pinfunction "8_8") (pintype "passive"))
    )
    (net (code "58") (name "unconnected-(J2-Pad9)") (class "Default")
      (node (ref "J2") (pin "9") (pinfunction "9_9") (pintype "passive"))
    )
    (net (code "59") (name "unconnected-(J2-Pad10)") (class "Default")
      (node (ref "J2") (pin "10") (pinfunction "10_10") (pintype "passive"))
    )
    (net (code "60") (name "unconnected-(J3-PAD1-PadNC1)") (class "Default")
      (node (ref "J3") (pin "NC1") (pinfunction "PAD1_NC1") (pintype "bidirectional"))
    )
    (net (code "61") (name "unconnected-(J3-PAD2-PadNC2)") (class "Default")
      (node (ref "J3") (pin "NC2") (pinfunction "PAD2_NC2") (pintype "bidirectional"))
    )
    (net (code "62") (name "unconnected-(U$2-RSV-PadRSV1)") (class "Default")
      (node (ref "U$2") (pin "RSV1") (pinfunction "RSV_RSV1") (pintype "bidirectional"))
    )
    (net (code "63") (name "unconnected-(U$2-RSV-PadRSV2)") (class "Default")
      (node (ref "U$2") (pin "RSV2") (pinfunction "RSV_RSV2") (pintype "bidirectional"))
    )
    (net (code "64") (name "unconnected-(U2-BP-Pad4)") (class "Default")
      (node (ref "U2") (pin "4") (pinfunction "BP_4") (pintype "input"))
    )
  )
)
